# Power.net
KiCad netlist of a schematic drawn in Altium Designer
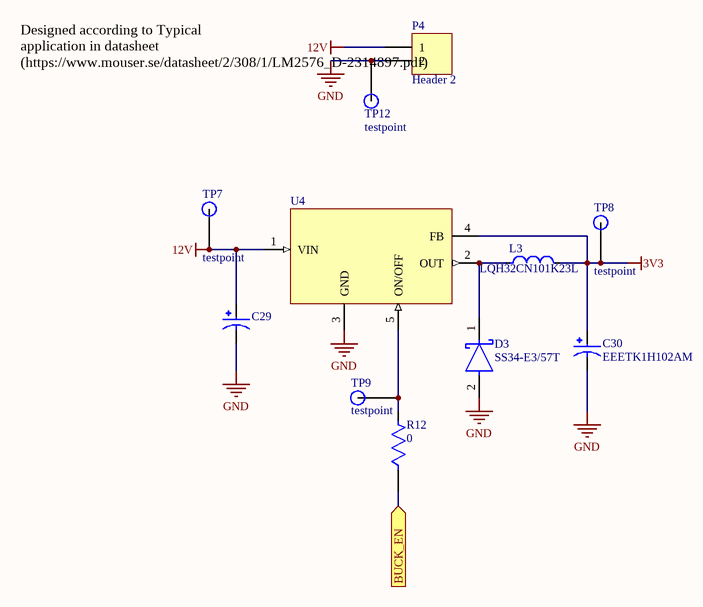
[diagram p0: Power.SchDoc]

(export (version "E")
  (design (tool "Eeschema 10.0.6"))
  (components
    (comp (ref "C29")
      (value "EEETC1C101P")
      (footprint "CAP_EEETC1C101P")
      (description "100µF 16V Aluminum Electrolytic Capacitors Radial, Can - SMD 200mOhm @ 100kHz 3000 Hrs @ 125°C")
      (fields (field (name "MF") "Panasonic"))
      (libsource (lib "Schlib") (part "EEETC1C101P"))
    )
    (comp (ref "C30")
      (value "EEETK1H102AM")
      (footprint "CAP_EEETK1H102AM")
      (description "1000µF 50V Aluminum Electrolytic Capacitors Radial, Can - SMD 140mOhm @ 100kHz 2000 Hrs @ 125°C")
      (fields (field (name "MF") "Panasonic Electronic") (field (name "MP") "EEE-TK1H102AM"))
      (libsource (lib "Schlib") (part "EEETK1H102AM"))
    )
    (comp (ref "D3")
      (value "SS34-E3/57T")
      (footprint "FP-95402-MFG")
      (description "DIODE SCHOTTKY 40V 3A DO214AB")
      (fields
        (field (name "MANUFACTURER") "Vishay")
        (field (name "OCTOPART") "https://octopart.com/ss34-e3%2F57t-vishay-39552907")
      )
      (libsource (lib "Altium Content Vault") (part "1d6ec82d83fb6aee721767c19dac4b9"))
    )
    (comp (ref "L3")
      (value "LQH32CN101K23L")
      (footprint "FP-LQH32CH_23-MFG")
      (description "Wire Wound Ferrite Inductor for Power Lines 100μH ±10% 4.55Ω 100mA 1210")
      (fields (field (name "TOLERANCE") "10%"))
      (libsource (lib "Altium Content Vault") (part "725321dda6339637d4d059423bc1c3c"))
    )
    (comp (ref "P4")
      (value "Header 2")
      (footprint "HDR1X2")
      (description "Header, 2-Pin")
      (fields (field (name "PUBLISHER") "Altium Limited"))
      (libsource (lib "Miscellaneous Connectors") (part "Header 2"))
    )
    (comp (ref "R12")
      (value "0")
      (footprint "FP-AC0603-MFG")
      (description "RES SMD 60.4 OHM 1% 1/10W 0603")
      (fields
        (field (name "MANUFACTURER PART NUMBER") "AC0603FR-0760R4L")
        (field (name "OCTOPART") "https://octopart.com/ac0603fr-0760r4l-yageo-71367350")
      )
      (libsource (lib "Altium Content Vault") (part "1029c3af85768c4190bb7ad29bc67b5"))
    )
    (comp (ref "TP7")
      (value "testpoint")
      (footprint "Testpoint")
      (libsource (lib "Schlib") (part "testpoint"))
    )
    (comp (ref "TP8")
      (value "testpoint")
      (footprint "Testpoint")
      (libsource (lib "Schlib") (part "testpoint"))
    )
    (comp (ref "TP9")
      (value "testpoint")
      (footprint "Testpoint")
      (libsource (lib "Schlib") (part "testpoint"))
    )
    (comp (ref "TP12")
      (value "testpoint")
      (footprint "Testpoint")
      (libsource (lib "Schlib") (part "testpoint"))
    )
    (comp (ref "U4")
      (value "LM2576D2TR4-3.3G")
      (footprint "D2PAK-5")
      (description "http://octopart.com/lm2576d2tr4-5g-on+semiconductor-46514222")
      (libsource (lib "Schlib") (part "LM2576D2TR4-3.3G"))
    )
  )
  (nets
    (net (code "1") (name "/BUCK_EN") (class "Default")
      (node (ref "R12") (pin "1") (pinfunction "1_1") (pintype "passive"))
    )
    (net (code "2") (name "3V3") (class "Default")
      (node (ref "C30") (pin "1") (pinfunction "1_1") (pintype "passive"))
      (node (ref "L3") (pin "2") (pinfunction "2_2") (pintype "passive"))
      (node (ref "TP8") (pin "1") (pinfunction "tp_1") (pintype "passive"))
      (node (ref "U4") (pin "4") (pinfunction "FB_4") (pintype "passive"))
    )
    (net (code "3") (name "12V") (class "Default")
      (node (ref "C29") (pin "1") (pinfunction "1_1") (pintype "passive"))
      (node (ref "P4") (pin "1") (pinfunction "1_1") (pintype "passive"))
      (node (ref "TP7") (pin "1") (pinfunction "tp_1") (pintype "passive"))
      (node (ref "U4") (pin "1") (pinfunction "VIN_1") (pintype "input"))
    )
    (net (code "4") (name "GND") (class "Default")
      (node (ref "C29") (pin "2") (pinfunction "2_2") (pintype "passive"))
      (node (ref "C30") (pin "2") (pinfunction "2_2") (pintype "passive"))
      (node (ref "D3") (pin "2") (pinfunction "A_2") (pintype "passive"))
      (node (ref "P4") (pin "2") (pinfunction "2_2") (pintype "passive"))
      (node (ref "TP12") (pin "1") (pinfunction "tp_1") (pintype "passive"))
      (node (ref "U4") (pin "3") (pinfunction "GND_3") (pintype "passive"))
    )
    (net (code "5") (name "Net-(D3-C)") (class "Default")
      (node (ref "D3") (pin "1") (pinfunction "C_1") (pintype "passive"))
      (node (ref "L3") (pin "1") (pinfunction "1_1") (pintype "passive"))
      (node (ref "U4") (pin "2") (pinfunction "OUT_2") (pintype "output"))
    )
    (net (code "6") (name "Net-(TP9-tp)") (class "Default")
      (node (ref "R12") (pin "2") (pinfunction "2_2") (pintype "passive"))
      (node (ref "TP9") (pin "1") (pinfunction "tp_1") (pintype "passive"))
      (node (ref "U4") (pin "5") (pinfunction "ON/OFF_5") (pintype "input"))
    )
  )
)
